# booster_Circuit.net
KiCad netlist of a schematic drawn in Altium Designer
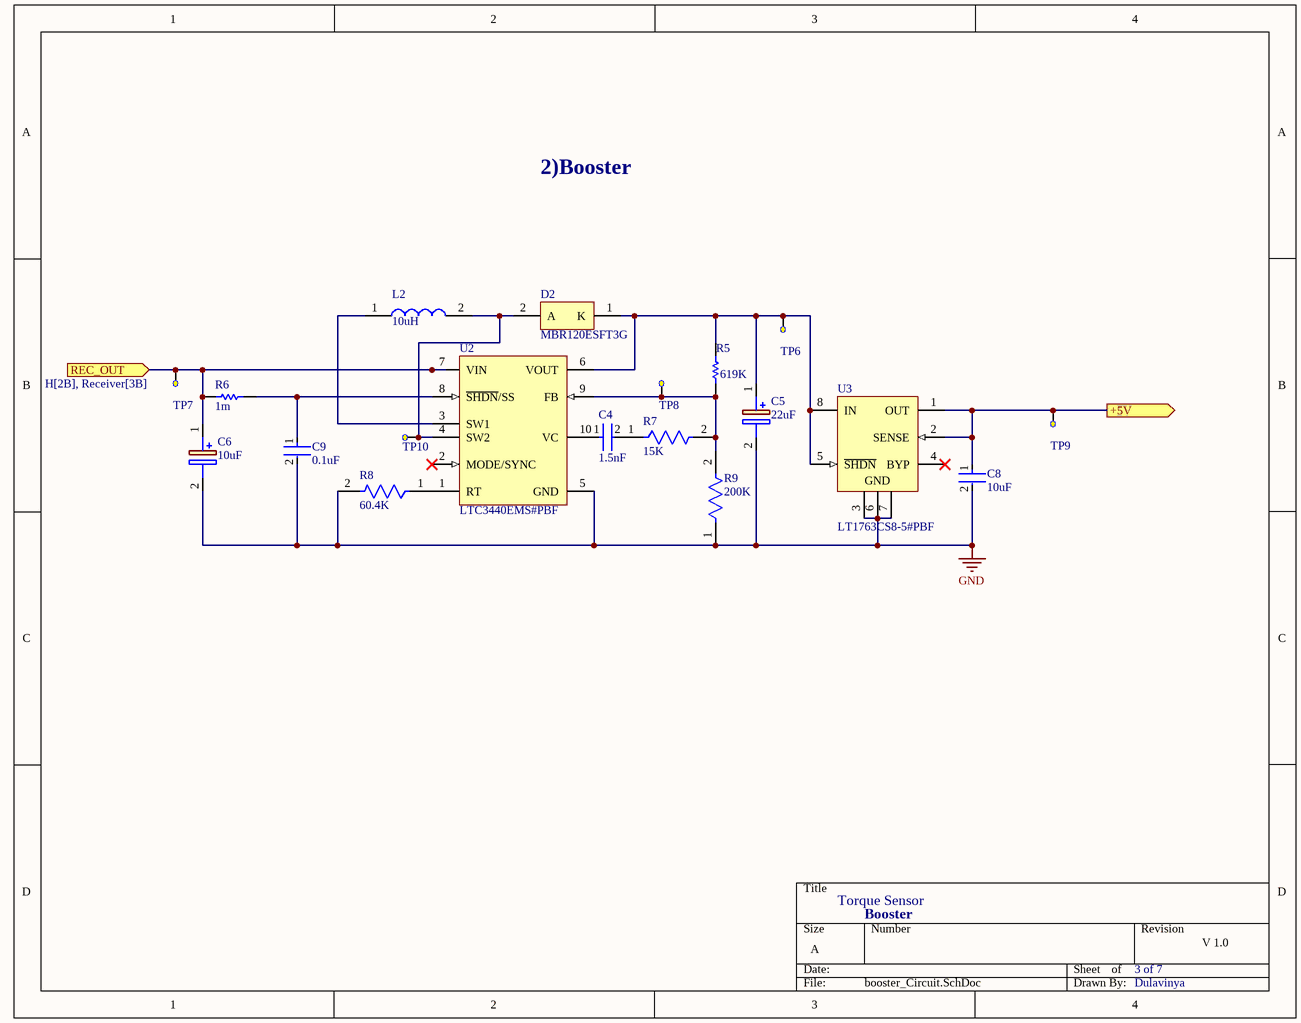
[diagram p0: booster_Circuit.SchDoc]

(export (version "E")
  (design (tool "Eeschema 10.0.6"))
  (components
    (comp (ref "C4")
      (value "1.5nF")
      (footprint "FP-CC0402-MFG")
      (description "CAP CER 1500PF 50V X7R 0402")
      (fields (field (name "MANUFACTURER") "YAGEO") (field (name "TOLERANCE") "0.1"))
      (libsource (lib "Altium Content Vault") (part "11868f565c42a9108669ba33697ecf6"))
    )
    (comp (ref "C5")
      (value "22uF")
      (footprint "SamacSys:EEE1AA220WR")
      (description "Capacitor Polarised")
      (fields
        (field (name "MANUFACTURER_PART_NUMBER") "EEE-FN1E220R")
        (field (name "MOUSER PART NUMBER") "667-EEE-FN1E220R")
      )
      (libsource (lib "*") (part "EEE-FN1E220R"))
    )
    (comp (ref "C6")
      (value "10uF")
      (footprint "SamacSys:EEE1AA220WR")
      (description "Capacitor Polarised")
      (fields
        (field (name "MANUFACTURER_PART_NUMBER") "EEE-FN1E220R")
        (field (name "MOUSER PART NUMBER") "667-EEE-FN1E220R")
      )
      (libsource (lib "*") (part "EEE-FN1E220R"))
    )
    (comp (ref "C8")
      (value "10uF")
      (footprint "FP-GRM155-0_05-MFG")
      (fields (field (name "VOLTAGE") "16V") (field (name "TOLERANCE") "10%"))
      (libsource (lib "Altium Content Vault") (part "b4654b650e69147ec39a6b967a45e02"))
    )
    (comp (ref "C9")
      (value "0.1uF")
      (footprint "FP-GRM155-0_05-MFG")
      (fields (field (name "VOLTAGE") "16V") (field (name "TOLERANCE") "10%"))
      (libsource (lib "Altium Content Vault") (part "b4654b650e69147ec39a6b967a45e02"))
    )
    (comp (ref "D2")
      (value "MBR120ESFT3G")
      (footprint "ONSC-SOD-123FL-2-498_V")
      (description "Schottky Power Rectifier, 2-Pin SOD-123, Pb-Free, Tape and Reel")
      (fields (field (name "MANUFACTURER") "On Semiconductor"))
      (libsource (lib "Altium Content Vault") (part "ONSC-D-K1A2-2_A"))
    )
    (comp (ref "L2")
      (value "10uH")
      (footprint "SamacSys:INDM6552X200N")
      (description "Inductor")
      (fields
        (field (name "MANUFACTURER_PART_NUMBER") "DO1606T-103MLC")
        (field (name "MOUSER PART NUMBER") "994-DO1606T-103MLC")
      )
      (libsource (lib "*") (part "DO1606T-103MLC"))
    )
    (comp (ref "R5")
      (value "619K")
      (footprint "RESC1005X40X25ML05T05")
      (fields (field (name "PART NUMBER") "ERJ-2RKF6193X") (field (name "MANUFACTURER") "Panasonic"))
      (libsource (lib "Altium Content Vault") (part "RES"))
    )
    (comp (ref "R6")
      (value "1m")
      (footprint "RESC2013X60X35ML10T20")
      (description "Chip Resistor, 1 KOhm, +/- 1%, 125 mW, -55 to 155 degC, 0805 (2012 Metric), RoHS, Tape and Reel")
      (fields (field (name "TOLERANCE") "1%") (field (name "MANUFACTURER") "Yageo"))
      (libsource (lib "Altium Content Vault") (part "RES-2"))
    )
    (comp (ref "R7")
      (value "15K")
      (footprint "FP-RT0402-MFG")
      (description "RES 15.0K OHM 1/16W .1% SMD 0402")
      (fields
        (field (name "OCTOPART") "https://octopart.com/rt0402bre0715kl-yageo-1259318")
        (field (name "MANUFACTURER") "Yageo")
      )
      (libsource (lib "Altium Content Vault") (part "1029c3af85768c4190bb7ad29bc67b5"))
    )
    (comp (ref "R8")
      (value "60.4K")
      (footprint "FP-ERJ2RK-MFG")
      (description "RES SMD 60.4K OHM 1% 1/10W 0402")
      (fields (field (name "TOLERANCE") "1%"))
      (libsource (lib "Altium Content Vault") (part "1029c3af85768c4190bb7ad29bc67b5"))
    )
    (comp (ref "R9")
      (value "200K")
      (footprint "FP-RT0402-MFG")
      (description "RES SMD 200K OHM 0.1% 1/16W 0402")
      (fields (field (name "TOLERANCE") "0.001") (field (name "MANUFACTURER") "Yageo"))
      (libsource (lib "Altium Content Vault") (part "1029c3af85768c4190bb7ad29bc67b5"))
    )
    (comp (ref "TP6")
      (value "Test point")
      (footprint "Test_point")
      (libsource (lib "Schlib1") (part "test_point"))
    )
    (comp (ref "TP7")
      (value "Test point")
      (footprint "Test_point")
      (libsource (lib "Schlib1") (part "test_point"))
    )
    (comp (ref "TP8")
      (value "Test point")
      (footprint "Test_point")
      (libsource (lib "Schlib1") (part "test_point"))
    )
    (comp (ref "TP9")
      (value "Test point")
      (footprint "Test_point")
      (libsource (lib "Schlib1") (part "test_point"))
    )
    (comp (ref "TP10")
      (value "Test point")
      (footprint "Test_point")
      (libsource (lib "Schlib1") (part "test_point"))
    )
    (comp (ref "U2")
      (value "LTC3440EMS#PBF")
      (footprint "LT-MS-10_M")
      (description "Micropower Synchronous Buck-Boost DC/DC Converter, 10-pin SOP (MS-10), -40 to 85 degC, Pb-Free")
      (fields (field (name "MANUFACTURER") "Linear Technology"))
      (libsource (lib "Altium Content Vault") (part "LT-LTC3440-MS-10"))
    )
    (comp (ref "U3")
      (value "LT1763CS8-5#PBF")
      (footprint "LT-S8-8_M")
      (fields (field (name "MANUFACTURER") "Linear Technology"))
      (libsource (lib "Altium Content Vault") (part "LT-LT1763-S8-8"))
    )
  )
  (nets
    (net (code "1") (name "/+5V") (class "Default")
      (node (ref "C8") (pin "1") (pinfunction "1_1") (pintype "passive"))
      (node (ref "TP9") (pin "TP?") (pinfunction "Test_point_TP?") (pintype "passive"))
      (node (ref "U3") (pin "1") (pinfunction "OUT_1") (pintype "power_in"))
      (node (ref "U3") (pin "2") (pinfunction "SENSE_2") (pintype "input"))
    )
    (net (code "2") (name "/REC_OUT") (class "Default")
      (node (ref "C6") (pin "1") (pinfunction "+_1") (pintype "passive"))
      (node (ref "R6") (pin "1") (pinfunction "1_1") (pintype "passive"))
      (node (ref "TP7") (pin "TP?") (pinfunction "Test_point_TP?") (pintype "passive"))
      (node (ref "U2") (pin "7") (pinfunction "VIN_7") (pintype "power_in"))
    )
    (net (code "3") (name "GND") (class "Default")
      (node (ref "C5") (pin "2") (pinfunction "-_2") (pintype "passive"))
      (node (ref "C6") (pin "2") (pinfunction "-_2") (pintype "passive"))
      (node (ref "C8") (pin "2") (pinfunction "2_2") (pintype "passive"))
      (node (ref "C9") (pin "2") (pinfunction "2_2") (pintype "passive"))
      (node (ref "R8") (pin "2") (pinfunction "2_2") (pintype "passive"))
      (node (ref "R9") (pin "1") (pinfunction "1_1") (pintype "passive"))
      (node (ref "U2") (pin "5") (pinfunction "GND_5") (pintype "power_in"))
      (node (ref "U3") (pin "3") (pinfunction "GND_3") (pintype "power_in"))
      (node (ref "U3") (pin "6") (pinfunction "GND_6") (pintype "power_in"))
      (node (ref "U3") (pin "7") (pinfunction "GND_7") (pintype "power_in"))
    )
    (net (code "4") (name "Net-(C4-Pad2)") (class "Default")
      (node (ref "C4") (pin "2") (pinfunction "2_2") (pintype "passive"))
      (node (ref "R7") (pin "1") (pinfunction "1_1") (pintype "passive"))
    )
    (net (code "5") (name "Net-(C5-+)") (class "Default")
      (node (ref "C5") (pin "1") (pinfunction "+_1") (pintype "passive"))
      (node (ref "D2") (pin "1") (pinfunction "K_1") (pintype "passive"))
      (node (ref "R5") (pin "2") (pinfunction "2_2") (pintype "passive"))
      (node (ref "TP6") (pin "TP?") (pinfunction "Test_point_TP?") (pintype "passive"))
      (node (ref "U2") (pin "6") (pinfunction "VOUT_6") (pintype "power_in"))
      (node (ref "U3") (pin "5") (pinfunction "~{SHDN}_5") (pintype "input"))
      (node (ref "U3") (pin "8") (pinfunction "IN_8") (pintype "power_in"))
    )
    (net (code "6") (name "Net-(D2-A)") (class "Default")
      (node (ref "D2") (pin "2") (pinfunction "A_2") (pintype "passive"))
      (node (ref "L2") (pin "2") (pinfunction "2_2") (pintype "passive"))
      (node (ref "TP10") (pin "TP?") (pinfunction "Test_point_TP?") (pintype "passive"))
      (node (ref "U2") (pin "4") (pinfunction "SW2_4") (pintype "passive"))
    )
    (net (code "7") (name "Net-(TP8-Test_point)") (class "Default")
      (node (ref "R5") (pin "1") (pinfunction "1_1") (pintype "passive"))
      (node (ref "R7") (pin "2") (pinfunction "2_2") (pintype "passive"))
      (node (ref "R9") (pin "2") (pinfunction "2_2") (pintype "passive"))
      (node (ref "TP8") (pin "TP?") (pinfunction "Test_point_TP?") (pintype "passive"))
      (node (ref "U2") (pin "9") (pinfunction "FB_9") (pintype "input"))
    )
    (net (code "8") (name "Net-(U2-RT)") (class "Default")
      (node (ref "R8") (pin "1") (pinfunction "1_1") (pintype "passive"))
      (node (ref "U2") (pin "1") (pinfunction "RT_1") (pintype "passive"))
    )
    (net (code "9") (name "Net-(U2-SW1)") (class "Default")
      (node (ref "L2") (pin "1") (pinfunction "1_1") (pintype "passive"))
      (node (ref "U2") (pin "3") (pinfunction "SW1_3") (pintype "passive"))
    )
    (net (code "10") (name "Net-(U2-VC)") (class "Default")
      (node (ref "C4") (pin "1") (pinfunction "1_1") (pintype "passive"))
      (node (ref "U2") (pin "10") (pinfunction "VC_10") (pintype "passive"))
    )
    (net (code "11") (name "Net-(U2-~{SHDN}{slash}SS)") (class "Default")
      (node (ref "C9") (pin "1") (pinfunction "1_1") (pintype "passive"))
      (node (ref "R6") (pin "2") (pinfunction "2_2") (pintype "passive"))
      (node (ref "U2") (pin "8") (pinfunction "~{SHDN}/SS_8") (pintype "input"))
    )
    (net (code "12") (name "unconnected-(U2-MODE{slash}SYNC-Pad2)") (class "Default")
      (node (ref "U2") (pin "2") (pinfunction "MODE/SYNC_2") (pintype "input+no_connect"))
    )
    (net (code "13") (name "unconnected-(U3-BYP-Pad4)") (class "Default")
      (node (ref "U3") (pin "4") (pinfunction "BYP_4") (pintype "passive+no_connect"))
    )
  )
)
